# NU32v7.net
KiCad netlist of a schematic drawn in EAGLE
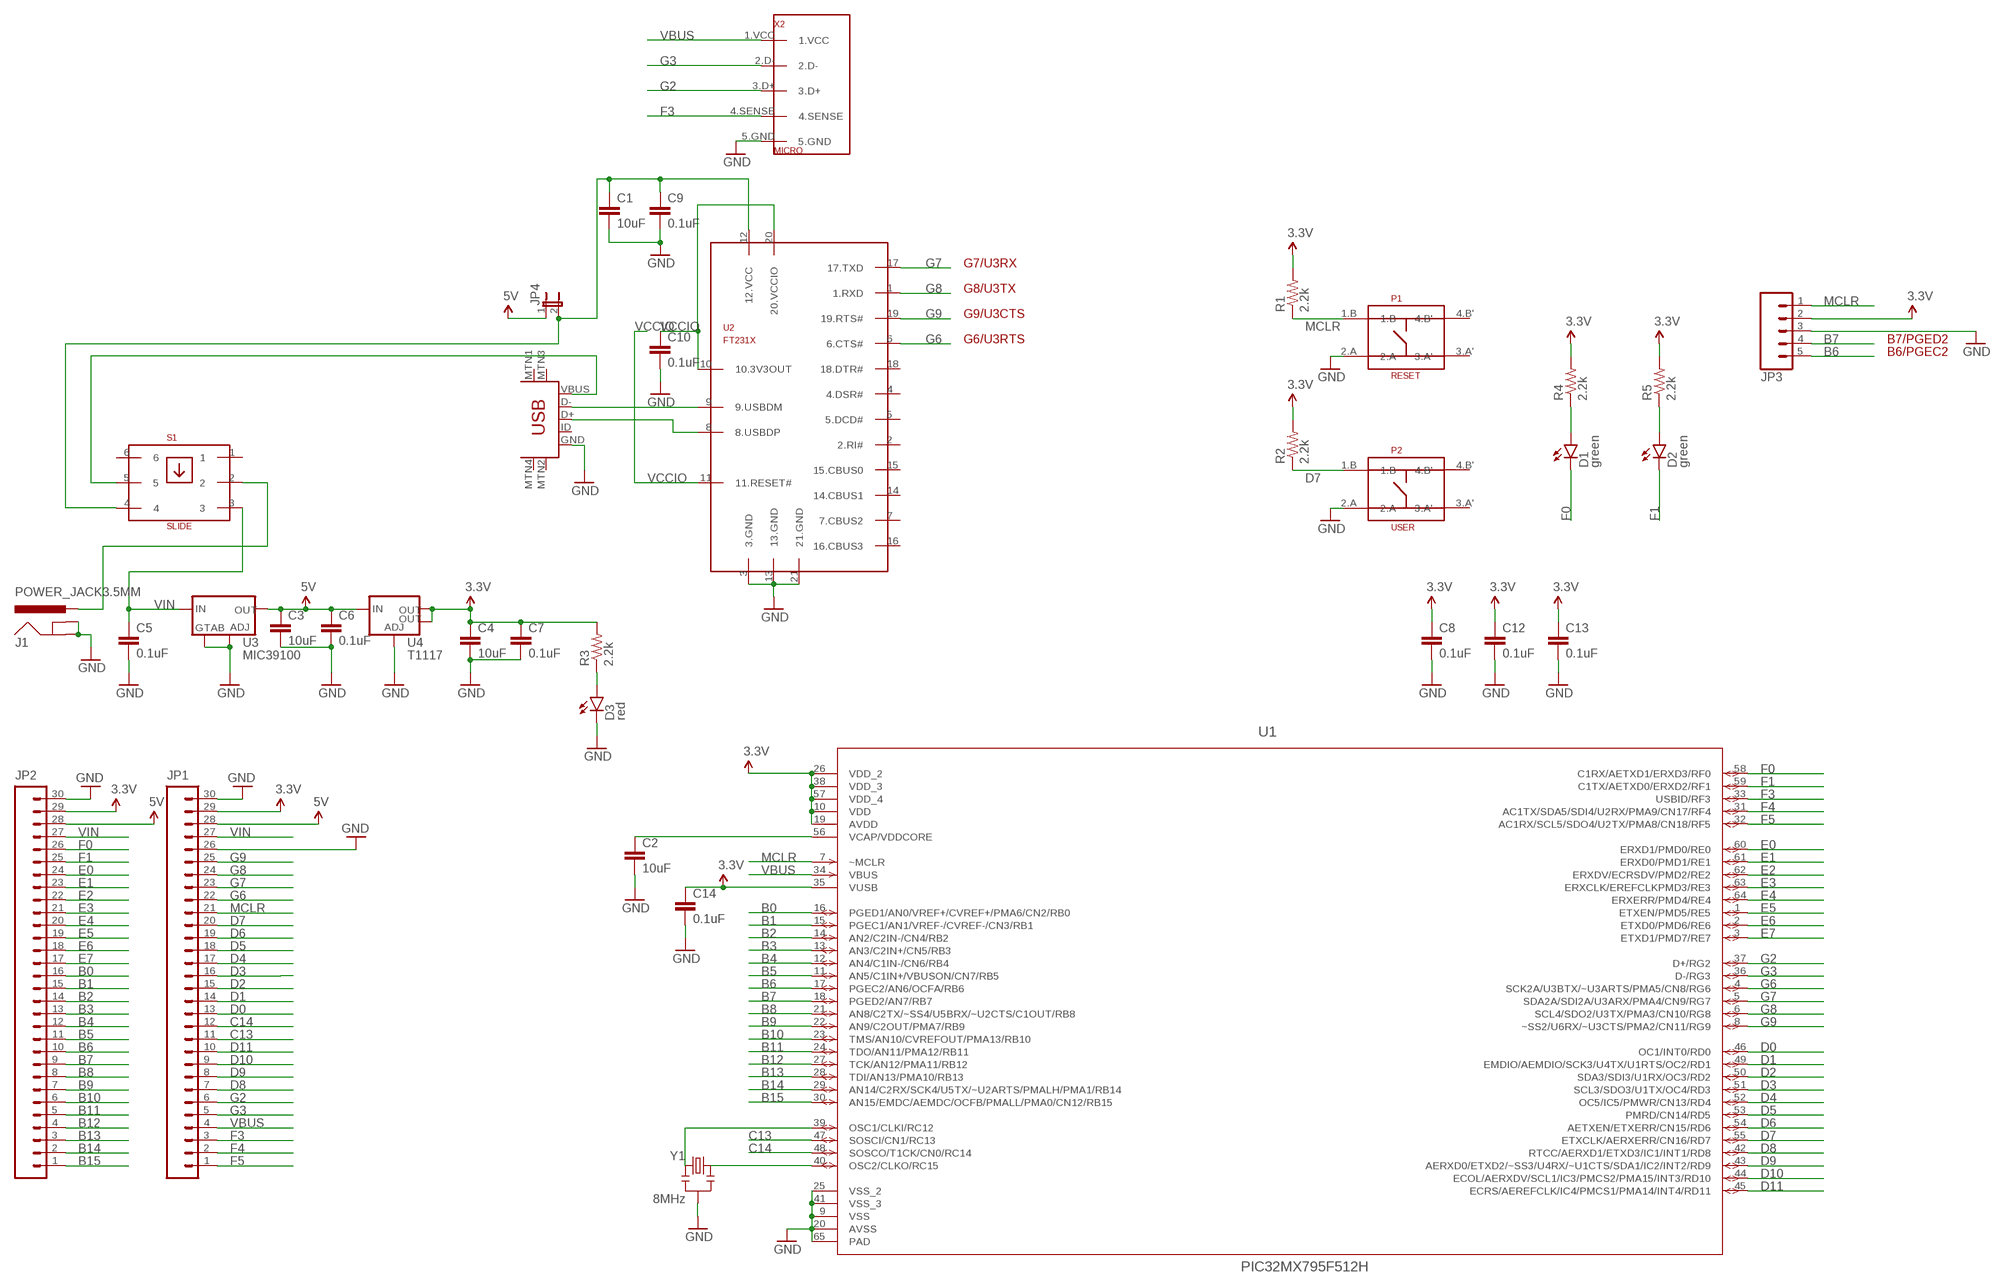
[diagram p0: schematic, sheet 1]

(export (version "E")
  (design (tool "Eeschema 10.0.6"))
  (components
    (comp (ref "C1")
      (value "10uF")
      (footprint "eagle-import:0603-CAP")
      (libsource (lib "eagle-import") (part "10UF-6.3V-20%(0603)"))
    )
    (comp (ref "C2")
      (value "10uF")
      (footprint "eagle-import:0603-CAP")
      (libsource (lib "eagle-import") (part "10UF-6.3V-20%(0603)"))
    )
    (comp (ref "C3")
      (value "10uF")
      (footprint "eagle-import:0603-CAP")
      (libsource (lib "eagle-import") (part "10UF-6.3V-20%(0603)"))
    )
    (comp (ref "C4")
      (value "10uF")
      (footprint "eagle-import:0603-CAP")
      (libsource (lib "eagle-import") (part "10UF-6.3V-20%(0603)"))
    )
    (comp (ref "C5")
      (value "0.1uF")
      (footprint "eagle-import:0603-CAP")
      (libsource (lib "eagle-import") (part "CAP0603-CAP"))
    )
    (comp (ref "C6")
      (value "0.1uF")
      (footprint "eagle-import:0603-CAP")
      (libsource (lib "eagle-import") (part "CAP0603-CAP"))
    )
    (comp (ref "C7")
      (value "0.1uF")
      (footprint "eagle-import:0603-CAP")
      (libsource (lib "eagle-import") (part "CAP0603-CAP"))
    )
    (comp (ref "C8")
      (value "0.1uF")
      (footprint "eagle-import:0603-CAP")
      (libsource (lib "eagle-import") (part "CAP0603-CAP"))
    )
    (comp (ref "C9")
      (value "0.1uF")
      (footprint "eagle-import:0603-CAP")
      (libsource (lib "eagle-import") (part "CAP0603-CAP"))
    )
    (comp (ref "C10")
      (value "0.1uF")
      (footprint "eagle-import:0603-CAP")
      (libsource (lib "eagle-import") (part "CAP0603-CAP"))
    )
    (comp (ref "C12")
      (value "0.1uF")
      (footprint "eagle-import:0603-CAP")
      (libsource (lib "eagle-import") (part "CAP0603-CAP"))
    )
    (comp (ref "C13")
      (value "0.1uF")
      (footprint "eagle-import:0603-CAP")
      (libsource (lib "eagle-import") (part "CAP0603-CAP"))
    )
    (comp (ref "C14")
      (value "0.1uF")
      (footprint "eagle-import:0603-CAP")
      (libsource (lib "eagle-import") (part "CAP0603-CAP"))
    )
    (comp (ref "D1")
      (value "green")
      (footprint "eagle-import:LED-0603")
      (libsource (lib "eagle-import") (part "LED0603"))
    )
    (comp (ref "D2")
      (value "green")
      (footprint "eagle-import:LED-0603")
      (libsource (lib "eagle-import") (part "LED0603"))
    )
    (comp (ref "D3")
      (value "red")
      (footprint "eagle-import:LED-0603")
      (libsource (lib "eagle-import") (part "LED0603"))
    )
    (comp (ref "J1")
      (value "POWER_JACK3.5MM")
      (footprint "eagle-import:POWER_JACK_3.5MM")
      (libsource (lib "eagle-import") (part "POWER_JACK3.5MM"))
    )
    (comp (ref "JP1")
      (value "M30NO_SILK")
      (footprint "eagle-import:1X30_NO_SILK")
      (libsource (lib "eagle-import") (part "M30NO_SILK"))
    )
    (comp (ref "JP2")
      (value "M30NO_SILK")
      (footprint "eagle-import:1X30_NO_SILK")
      (libsource (lib "eagle-import") (part "M30NO_SILK"))
    )
    (comp (ref "JP3")
      (value "M05PTH")
      (footprint "eagle-import:1X05")
      (libsource (lib "eagle-import") (part "M05PTH"))
    )
    (comp (ref "JP4")
      (value "JUMPER-2SMD-NO")
      (footprint "eagle-import:SJ_2S-NO")
      (libsource (lib "eagle-import") (part "JUMPER-2SMD-NO"))
    )
    (comp (ref "P1")
      (value "RESET")
      (footprint "eagle-import:MOM_SW")
      (libsource (lib "eagle-import") (part "MOM_SW"))
    )
    (comp (ref "P2")
      (value "USER")
      (footprint "eagle-import:MOM_SW")
      (libsource (lib "eagle-import") (part "MOM_SW"))
    )
    (comp (ref "R1")
      (value "2.2k")
      (footprint "eagle-import:0603-RES")
      (libsource (lib "eagle-import") (part "RESISTOR0603"))
    )
    (comp (ref "R2")
      (value "2.2k")
      (footprint "eagle-import:0603-RES")
      (libsource (lib "eagle-import") (part "RESISTOR0603"))
    )
    (comp (ref "R3")
      (value "2.2k")
      (footprint "eagle-import:0603-RES")
      (libsource (lib "eagle-import") (part "RESISTOR0603"))
    )
    (comp (ref "R4")
      (value "2.2k")
      (footprint "eagle-import:0603-RES")
      (libsource (lib "eagle-import") (part "RESISTOR0603"))
    )
    (comp (ref "R5")
      (value "2.2k")
      (footprint "eagle-import:0603-RES")
      (libsource (lib "eagle-import") (part "RESISTOR0603"))
    )
    (comp (ref "S1")
      (value "SLIDE")
      (footprint "eagle-import:SLIDE_SW")
      (libsource (lib "eagle-import") (part "SLIDE_SW"))
    )
    (comp (ref "U1")
      (value "PIC32MX795F512H")
      (footprint "eagle-import:QFN50P900X900X100-65N")
      (libsource (lib "eagle-import") (part "PIC32MX795F512H-80I/PTQFN"))
    )
    (comp (ref "U2")
      (value "FT231X")
      (footprint "eagle-import:QFN50P400X400X100-21N")
      (libsource (lib "eagle-import") (part "FT231X"))
    )
    (comp (ref "U3")
      (value "MIC39100")
      (footprint "eagle-import:SOT223")
      (libsource (lib "eagle-import") (part "MIC39100"))
    )
    (comp (ref "U4")
      (value "T1117")
      (footprint "eagle-import:SOT223")
      (libsource (lib "eagle-import") (part "V_REG_LM1117SOT223"))
    )
    (comp (ref "X1")
      (value "MINI")
      (footprint "eagle-import:USB-MINIB")
      (libsource (lib "eagle-import") (part "USB-MINIB-5PIN"))
    )
    (comp (ref "X2")
      (value "MICRO")
      (footprint "eagle-import:MICROUSB")
      (libsource (lib "eagle-import") (part "MICROUSB"))
    )
    (comp (ref "Y1")
      (value "8MHz")
      (footprint "eagle-import:RESONATOR-SMD")
      (libsource (lib "eagle-import") (part "RESONATORSMD"))
    )
  )
  (nets
    (net (code "1") (name "/B0") (class "Default")
      (node (ref "JP2") (pin "16") (pinfunction "16_16") (pintype "passive"))
      (node (ref "U1") (pin "16") (pinfunction "PGED1/AN0/VREF+/CVREF+/PMA6/CN2/RB0_16") (pintype "bidirectional"))
    )
    (net (code "2") (name "/B1") (class "Default")
      (node (ref "JP2") (pin "15") (pinfunction "15_15") (pintype "passive"))
      (node (ref "U1") (pin "15") (pinfunction "PGEC1/AN1/VREF-/CVREF-/CN3/RB1_15") (pintype "bidirectional"))
    )
    (net (code "3") (name "/B2") (class "Default")
      (node (ref "JP2") (pin "14") (pinfunction "14_14") (pintype "passive"))
      (node (ref "U1") (pin "14") (pinfunction "AN2/C2IN-/CN4/RB2_14") (pintype "bidirectional"))
    )
    (net (code "4") (name "/B3") (class "Default")
      (node (ref "JP2") (pin "13") (pinfunction "13_13") (pintype "passive"))
      (node (ref "U1") (pin "13") (pinfunction "AN3/C2IN+/CN5/RB3_13") (pintype "bidirectional"))
    )
    (net (code "5") (name "/B4") (class "Default")
      (node (ref "JP2") (pin "12") (pinfunction "12_12") (pintype "passive"))
      (node (ref "U1") (pin "12") (pinfunction "AN4/C1IN-/CN6/RB4_12") (pintype "bidirectional"))
    )
    (net (code "6") (name "/B5") (class "Default")
      (node (ref "JP2") (pin "11") (pinfunction "11_11") (pintype "passive"))
      (node (ref "U1") (pin "11") (pinfunction "AN5/C1IN+/VBUSON/CN7/RB5_11") (pintype "bidirectional"))
    )
    (net (code "7") (name "/B6") (class "Default")
      (node (ref "JP2") (pin "10") (pinfunction "10_10") (pintype "passive"))
      (node (ref "JP3") (pin "5") (pinfunction "5_5") (pintype "passive"))
      (node (ref "U1") (pin "17") (pinfunction "PGEC2/AN6/OCFA/RB6_17") (pintype "bidirectional"))
    )
    (net (code "8") (name "/B7") (class "Default")
      (node (ref "JP2") (pin "9") (pinfunction "9_9") (pintype "passive"))
      (node (ref "JP3") (pin "4") (pinfunction "4_4") (pintype "passive"))
      (node (ref "U1") (pin "18") (pinfunction "PGED2/AN7/RB7_18") (pintype "bidirectional"))
    )
    (net (code "9") (name "/B8") (class "Default")
      (node (ref "JP2") (pin "8") (pinfunction "8_8") (pintype "passive"))
      (node (ref "U1") (pin "21") (pinfunction "AN8/C2TX/~{SS4/U5BRX/}U2CTS/C1OUT/RB8_21") (pintype "bidirectional"))
    )
    (net (code "10") (name "/B9") (class "Default")
      (node (ref "JP2") (pin "7") (pinfunction "7_7") (pintype "passive"))
      (node (ref "U1") (pin "22") (pinfunction "AN9/C2OUT/PMA7/RB9_22") (pintype "bidirectional"))
    )
    (net (code "11") (name "/B10") (class "Default")
      (node (ref "JP2") (pin "6") (pinfunction "6_6") (pintype "passive"))
      (node (ref "U1") (pin "23") (pinfunction "TMS/AN10/CVREFOUT/PMA13/RB10_23") (pintype "bidirectional"))
    )
    (net (code "12") (name "/B11") (class "Default")
      (node (ref "JP2") (pin "5") (pinfunction "5_5") (pintype "passive"))
      (node (ref "U1") (pin "24") (pinfunction "TDO/AN11/PMA12/RB11_24") (pintype "bidirectional"))
    )
    (net (code "13") (name "/B12") (class "Default")
      (node (ref "JP2") (pin "4") (pinfunction "4_4") (pintype "passive"))
      (node (ref "U1") (pin "27") (pinfunction "TCK/AN12/PMA11/RB12_27") (pintype "bidirectional"))
    )
    (net (code "14") (name "/B13") (class "Default")
      (node (ref "JP2") (pin "3") (pinfunction "3_3") (pintype "passive"))
      (node (ref "U1") (pin "28") (pinfunction "TDI/AN13/PMA10/RB13_28") (pintype "bidirectional"))
    )
    (net (code "15") (name "/B14") (class "Default")
      (node (ref "JP2") (pin "2") (pinfunction "2_2") (pintype "passive"))
      (node (ref "U1") (pin "29") (pinfunction "AN14/C2RX/SCK4/U5TX/~{U2ARTS/PMALH/PMA1/RB14}_29") (pintype "bidirectional"))
    )
    (net (code "16") (name "/B15") (class "Default")
      (node (ref "JP2") (pin "1") (pinfunction "1_1") (pintype "passive"))
      (node (ref "U1") (pin "30") (pinfunction "AN15/EMDC/AEMDC/OCFB/PMALL/PMA0/CN12/RB15_30") (pintype "bidirectional"))
    )
    (net (code "17") (name "/C13") (class "Default")
      (node (ref "JP1") (pin "11") (pinfunction "11_11") (pintype "passive"))
      (node (ref "U1") (pin "47") (pinfunction "SOSCI/CN1/RC13_47") (pintype "bidirectional"))
    )
    (net (code "18") (name "/C14") (class "Default")
      (node (ref "JP1") (pin "12") (pinfunction "12_12") (pintype "passive"))
      (node (ref "U1") (pin "48") (pinfunction "SOSCO/T1CK/CN0/RC14_48") (pintype "bidirectional"))
    )
    (net (code "19") (name "/D0") (class "Default")
      (node (ref "JP1") (pin "13") (pinfunction "13_13") (pintype "passive"))
      (node (ref "U1") (pin "46") (pinfunction "OC1/INT0/RD0_46") (pintype "bidirectional"))
    )
    (net (code "20") (name "/D1") (class "Default")
      (node (ref "JP1") (pin "14") (pinfunction "14_14") (pintype "passive"))
      (node (ref "U1") (pin "49") (pinfunction "EMDIO/AEMDIO/SCK3/U4TX/U1RTS/OC2/RD1_49") (pintype "bidirectional"))
    )
    (net (code "21") (name "/D2") (class "Default")
      (node (ref "JP1") (pin "15") (pinfunction "15_15") (pintype "passive"))
      (node (ref "U1") (pin "50") (pinfunction "SDA3/SDI3/U1RX/OC3/RD2_50") (pintype "bidirectional"))
    )
    (net (code "22") (name "/D3") (class "Default")
      (node (ref "JP1") (pin "16") (pinfunction "16_16") (pintype "passive"))
      (node (ref "U1") (pin "51") (pinfunction "SCL3/SDO3/U1TX/OC4/RD3_51") (pintype "bidirectional"))
    )
    (net (code "23") (name "/D4") (class "Default")
      (node (ref "JP1") (pin "17") (pinfunction "17_17") (pintype "passive"))
      (node (ref "U1") (pin "52") (pinfunction "OC5/IC5/PMWR/CN13/RD4_52") (pintype "bidirectional"))
    )
    (net (code "24") (name "/D5") (class "Default")
      (node (ref "JP1") (pin "18") (pinfunction "18_18") (pintype "passive"))
      (node (ref "U1") (pin "53") (pinfunction "PMRD/CN14/RD5_53") (pintype "bidirectional"))
    )
    (net (code "25") (name "/D6") (class "Default")
      (node (ref "JP1") (pin "19") (pinfunction "19_19") (pintype "passive"))
      (node (ref "U1") (pin "54") (pinfunction "AETXEN/ETXERR/CN15/RD6_54") (pintype "bidirectional"))
    )
    (net (code "26") (name "/D7") (class "Default")
      (node (ref "JP1") (pin "20") (pinfunction "20_20") (pintype "passive"))
      (node (ref "P2") (pin "1.B") (pinfunction "1.B_1.B") (pintype "bidirectional"))
      (node (ref "R2") (pin "1") (pinfunction "1_1") (pintype "passive"))
      (node (ref "U1") (pin "55") (pinfunction "ETXCLK/AERXERR/CN16/RD7_55") (pintype "bidirectional"))
    )
    (net (code "27") (name "/D8") (class "Default")
      (node (ref "JP1") (pin "7") (pinfunction "7_7") (pintype "passive"))
      (node (ref "U1") (pin "42") (pinfunction "RTCC/AERXD1/ETXD3/IC1/INT1/RD8_42") (pintype "bidirectional"))
    )
    (net (code "28") (name "/D9") (class "Default")
      (node (ref "JP1") (pin "8") (pinfunction "8_8") (pintype "passive"))
      (node (ref "U1") (pin "43") (pinfunction "AERXD0/ETXD2/~{SS3/U4RX/}U1CTS/SDA1/IC2/INT2/RD9_43") (pintype "bidirectional"))
    )
    (net (code "29") (name "/D10") (class "Default")
      (node (ref "JP1") (pin "9") (pinfunction "9_9") (pintype "passive"))
      (node (ref "U1") (pin "44") (pinfunction "ECOL/AERXDV/SCL1/IC3/PMCS2/PMA15/INT3/RD10_44") (pintype "bidirectional"))
    )
    (net (code "30") (name "/D11") (class "Default")
      (node (ref "JP1") (pin "10") (pinfunction "10_10") (pintype "passive"))
      (node (ref "U1") (pin "45") (pinfunction "ECRS/AEREFCLK/IC4/PMCS1/PMA14/INT4/RD11_45") (pintype "bidirectional"))
    )
    (net (code "31") (name "/E0") (class "Default")
      (node (ref "JP2") (pin "24") (pinfunction "24_24") (pintype "passive"))
      (node (ref "U1") (pin "60") (pinfunction "ERXD1/PMD0/RE0_60") (pintype "bidirectional"))
    )
    (net (code "32") (name "/E1") (class "Default")
      (node (ref "JP2") (pin "23") (pinfunction "23_23") (pintype "passive"))
      (node (ref "U1") (pin "61") (pinfunction "ERXD0/PMD1/RE1_61") (pintype "bidirectional"))
    )
    (net (code "33") (name "/E2") (class "Default")
      (node (ref "JP2") (pin "22") (pinfunction "22_22") (pintype "passive"))
      (node (ref "U1") (pin "62") (pinfunction "ERXDV/ECRSDV/PMD2/RE2_62") (pintype "bidirectional"))
    )
    (net (code "34") (name "/E3") (class "Default")
      (node (ref "JP2") (pin "21") (pinfunction "21_21") (pintype "passive"))
      (node (ref "U1") (pin "63") (pinfunction "ERXCLK/EREFCLKPMD3/RE3_63") (pintype "bidirectional"))
    )
    (net (code "35") (name "/E4") (class "Default")
      (node (ref "JP2") (pin "20") (pinfunction "20_20") (pintype "passive"))
      (node (ref "U1") (pin "64") (pinfunction "ERXERR/PMD4/RE4_64") (pintype "bidirectional"))
    )
    (net (code "36") (name "/E5") (class "Default")
      (node (ref "JP2") (pin "19") (pinfunction "19_19") (pintype "passive"))
      (node (ref "U1") (pin "1") (pinfunction "ETXEN/PMD5/RE5_1") (pintype "bidirectional"))
    )
    (net (code "37") (name "/E6") (class "Default")
      (node (ref "JP2") (pin "18") (pinfunction "18_18") (pintype "passive"))
      (node (ref "U1") (pin "2") (pinfunction "ETXD0/PMD6/RE6_2") (pintype "bidirectional"))
    )
    (net (code "38") (name "/E7") (class "Default")
      (node (ref "JP2") (pin "17") (pinfunction "17_17") (pintype "passive"))
      (node (ref "U1") (pin "3") (pinfunction "ETXD1/PMD7/RE7_3") (pintype "bidirectional"))
    )
    (net (code "39") (name "/F0") (class "Default")
      (node (ref "D1") (pin "C") (pinfunction "C_C") (pintype "passive"))
      (node (ref "JP2") (pin "26") (pinfunction "26_26") (pintype "passive"))
      (node (ref "U1") (pin "58") (pinfunction "C1RX/AETXD1/ERXD3/RF0_58") (pintype "bidirectional"))
    )
    (net (code "40") (name "/F1") (class "Default")
      (node (ref "D2") (pin "C") (pinfunction "C_C") (pintype "passive"))
      (node (ref "JP2") (pin "25") (pinfunction "25_25") (pintype "passive"))
      (node (ref "U1") (pin "59") (pinfunction "C1TX/AETXD0/ERXD2/RF1_59") (pintype "bidirectional"))
    )
    (net (code "41") (name "/F3") (class "Default")
      (node (ref "JP1") (pin "3") (pinfunction "3_3") (pintype "passive"))
      (node (ref "U1") (pin "33") (pinfunction "USBID/RF3_33") (pintype "bidirectional"))
      (node (ref "X2") (pin "4.SENSE") (pinfunction "4.SENSE_4.SENSE") (pintype "bidirectional"))
    )
    (net (code "42") (name "/F4") (class "Default")
      (node (ref "JP1") (pin "2") (pinfunction "2_2") (pintype "passive"))
      (node (ref "U1") (pin "31") (pinfunction "AC1TX/SDA5/SDI4/U2RX/PMA9/CN17/RF4_31") (pintype "bidirectional"))
    )
    (net (code "43") (name "/F5") (class "Default")
      (node (ref "JP1") (pin "1") (pinfunction "1_1") (pintype "passive"))
      (node (ref "U1") (pin "32") (pinfunction "AC1RX/SCL5/SDO4/U2TX/PMA8/CN18/RF5_32") (pintype "bidirectional"))
    )
    (net (code "44") (name "/G2") (class "Default")
      (node (ref "JP1") (pin "6") (pinfunction "6_6") (pintype "passive"))
      (node (ref "U1") (pin "37") (pinfunction "D+/RG2_37") (pintype "bidirectional"))
      (node (ref "X2") (pin "3.D+") (pinfunction "3.D+_3.D+") (pintype "bidirectional"))
    )
    (net (code "45") (name "/G3") (class "Default")
      (node (ref "JP1") (pin "5") (pinfunction "5_5") (pintype "passive"))
      (node (ref "U1") (pin "36") (pinfunction "D-/RG3_36") (pintype "bidirectional"))
      (node (ref "X2") (pin "2.D-") (pinfunction "2.D-_2.D-") (pintype "bidirectional"))
    )
    (net (code "46") (name "/G6") (class "Default")
      (node (ref "JP1") (pin "22") (pinfunction "22_22") (pintype "passive"))
      (node (ref "U1") (pin "4") (pinfunction "SCK2A/U3BTX/~{U3ARTS/PMA5/CN8/RG6}_4") (pintype "bidirectional"))
      (node (ref "U2") (pin "6") (pinfunction "6.CTS#_6") (pintype "bidirectional"))
    )
    (net (code "47") (name "/G7") (class "Default")
      (node (ref "JP1") (pin "23") (pinfunction "23_23") (pintype "passive"))
      (node (ref "U1") (pin "5") (pinfunction "SDA2A/SDI2A/U3ARX/PMA4/CN9/RG7_5") (pintype "bidirectional"))
      (node (ref "U2") (pin "17") (pinfunction "17.TXD_17") (pintype "bidirectional"))
    )
    (net (code "48") (name "/G8") (class "Default")
      (node (ref "JP1") (pin "24") (pinfunction "24_24") (pintype "passive"))
      (node (ref "U1") (pin "6") (pinfunction "SCL4/SDO2/U3TX/PMA3/CN10/RG8_6") (pintype "bidirectional"))
      (node (ref "U2") (pin "1") (pinfunction "1.RXD_1") (pintype "bidirectional"))
    )
    (net (code "49") (name "/G9") (class "Default")
      (node (ref "JP1") (pin "25") (pinfunction "25_25") (pintype "passive"))
      (node (ref "U1") (pin "8") (pinfunction "~{SS2/U6RX/}U3CTS/PMA2/CN11/RG9_8") (pintype "bidirectional"))
      (node (ref "U2") (pin "19") (pinfunction "19.RTS#_19") (pintype "bidirectional"))
    )
    (net (code "50") (name "/MCLR") (class "Default")
      (node (ref "JP1") (pin "21") (pinfunction "21_21") (pintype "passive"))
      (node (ref "JP3") (pin "1") (pinfunction "1_1") (pintype "passive"))
      (node (ref "P1") (pin "1.B") (pinfunction "1.B_1.B") (pintype "bidirectional"))
      (node (ref "R1") (pin "1") (pinfunction "1_1") (pintype "passive"))
      (node (ref "U1") (pin "7") (pinfunction "~{MCLR}_7") (pintype "input"))
    )
    (net (code "51") (name "/VBUS") (class "Default")
      (node (ref "JP1") (pin "4") (pinfunction "4_4") (pintype "passive"))
      (node (ref "U1") (pin "34") (pinfunction "VBUS_34") (pintype "input"))
      (node (ref "X2") (pin "1.VCC") (pinfunction "1.VCC_1.VCC") (pintype "bidirectional"))
    )
    (net (code "52") (name "/VCCIO") (class "Default")
      (node (ref "C10") (pin "1") (pinfunction "1_1") (pintype "passive"))
      (node (ref "U2") (pin "10") (pinfunction "10.3V3OUT_10") (pintype "bidirectional"))
      (node (ref "U2") (pin "11") (pinfunction "11.RESET#_11") (pintype "bidirectional"))
      (node (ref "U2") (pin "20") (pinfunction "20.VCCIO_20") (pintype "bidirectional"))
    )
    (net (code "53") (name "/VIN") (class "Default")
      (node (ref "C5") (pin "1") (pinfunction "1_1") (pintype "passive"))
      (node (ref "JP1") (pin "27") (pinfunction "27_27") (pintype "passive"))
      (node (ref "JP2") (pin "27") (pinfunction "27_27") (pintype "passive"))
      (node (ref "S1") (pin "3") (pinfunction "3_3") (pintype "bidirectional"))
      (node (ref "U3") (pin "1") (pinfunction "IN_1") (pintype "input"))
    )
    (net (code "54") (name "3.3V") (class "Default")
      (node (ref "C12") (pin "1") (pinfunction "1_1") (pintype "passive"))
      (node (ref "C13") (pin "1") (pinfunction "1_1") (pintype "passive"))
      (node (ref "C14") (pin "1") (pinfunction "1_1") (pintype "passive"))
      (node (ref "C4") (pin "1") (pinfunction "1_1") (pintype "passive"))
      (node (ref "C7") (pin "1") (pinfunction "1_1") (pintype "passive"))
      (node (ref "C8") (pin "1") (pinfunction "1_1") (pintype "passive"))
      (node (ref "JP1") (pin "29") (pinfunction "29_29") (pintype "passive"))
      (node (ref "JP2") (pin "29") (pinfunction "29_29") (pintype "passive"))
      (node (ref "JP3") (pin "2") (pinfunction "2_2") (pintype "passive"))
      (node (ref "R1") (pin "2") (pinfunction "2_2") (pintype "passive"))
      (node (ref "R2") (pin "2") (pinfunction "2_2") (pintype "passive"))
      (node (ref "R3") (pin "2") (pinfunction "2_2") (pintype "passive"))
      (node (ref "R4") (pin "2") (pinfunction "2_2") (pintype "passive"))
      (node (ref "R5") (pin "2") (pinfunction "2_2") (pintype "passive"))
      (node (ref "U1") (pin "10") (pinfunction "VDD_10") (pintype "power_in"))
      (node (ref "U1") (pin "19") (pinfunction "AVDD_19") (pintype "power_in"))
      (node (ref "U1") (pin "26") (pinfunction "VDD_2_26") (pintype "power_in"))
      (node (ref "U1") (pin "35") (pinfunction "VUSB_35") (pintype "power_in"))
      (node (ref "U1") (pin "38") (pinfunction "VDD_3_38") (pintype "power_in"))
      (node (ref "U1") (pin "57") (pinfunction "VDD_4_57") (pintype "power_in"))
      (node (ref "U4") (pin "2") (pinfunction "OUT_2") (pintype "output"))
      (node (ref "U4") (pin "4") (pinfunction "OUT_4") (pintype "output"))
    )
    (net (code "55") (name "5V") (class "Default")
      (node (ref "C3") (pin "1") (pinfunction "1_1") (pintype "passive"))
      (node (ref "C6") (pin "1") (pinfunction "1_1") (pintype "passive"))
      (node (ref "JP1") (pin "28") (pinfunction "28_28") (pintype "passive"))
      (node (ref "JP2") (pin "28") (pinfunction "28_28") (pintype "passive"))
      (node (ref "JP4") (pin "1") (pinfunction "1_1") (pintype "passive"))
      (node (ref "U3") (pin "3") (pinfunction "OUT_3") (pintype "output"))
      (node (ref "U4") (pin "3") (pinfunction "IN_3") (pintype "input"))
    )
    (net (code "56") (name "GND") (class "Default")
      (node (ref "C1") (pin "2") (pinfunction "2_2") (pintype "passive"))
      (node (ref "C10") (pin "2") (pinfunction "2_2") (pintype "passive"))
      (node (ref "C12") (pin "2") (pinfunction "2_2") (pintype "passive"))
      (node (ref "C13") (pin "2") (pinfunction "2_2") (pintype "passive"))
      (node (ref "C14") (pin "2") (pinfunction "2_2") (pintype "passive"))
      (node (ref "C2") (pin "2") (pinfunction "2_2") (pintype "passive"))
      (node (ref "C3") (pin "2") (pinfunction "2_2") (pintype "passive"))
      (node (ref "C4") (pin "2") (pinfunction "2_2") (pintype "passive"))
      (node (ref "C5") (pin "2") (pinfunction "2_2") (pintype "passive"))
      (node (ref "C6") (pin "2") (pinfunction "2_2") (pintype "passive"))
      (node (ref "C7") (pin "2") (pinfunction "2_2") (pintype "passive"))
      (node (ref "C8") (pin "2") (pinfunction "2_2") (pintype "passive"))
      (node (ref "C9") (pin "2") (pinfunction "2_2") (pintype "passive"))
      (node (ref "D3") (pin "C") (pinfunction "C_C") (pintype "passive"))
      (node (ref "J1") (pin "2.GND") (pinfunction "GND_2.GND") (pintype "bidirectional"))
      (node (ref "J1") (pin "3.GNDBREAK") (pinfunction "GNDBREAK_3.GNDBREAK") (pintype "bidirectional"))
      (node (ref "JP1") (pin "26") (pinfunction "26_26") (pintype "passive"))
      (node (ref "JP1") (pin "30") (pinfunction "30_30") (pintype "passive"))
      (node (ref "JP2") (pin "30") (pinfunction "30_30") (pintype "passive"))
      (node (ref "JP3") (pin "3") (pinfunction "3_3") (pintype "passive"))
      (node (ref "P1") (pin "2.A") (pinfunction "2.A_2.A") (pintype "bidirectional"))
      (node (ref "P2") (pin "2.A") (pinfunction "2.A_2.A") (pintype "bidirectional"))
      (node (ref "U1") (pin "20") (pinfunction "AVSS_20") (pintype "power_in"))
      (node (ref "U1") (pin "25") (pinfunction "VSS_2_25") (pintype "power_in"))
      (node (ref "U1") (pin "41") (pinfunction "VSS_3_41") (pintype "power_in"))
      (node (ref "U1") (pin "65") (pinfunction "PAD_65") (pintype "bidirectional"))
      (node (ref "U1") (pin "9") (pinfunction "VSS_9") (pintype "power_in"))
      (node (ref "U2") (pin "13") (pinfunction "13.GND_13") (pintype "bidirectional"))
      (node (ref "U2") (pin "21") (pinfunction "21.GND_21") (pintype "bidirectional"))
      (node (ref "U2") (pin "3") (pinfunction "3.GND_3") (pintype "bidirectional"))
      (node (ref "U3") (pin "2") (pinfunction "ADJ_2") (pintype "input"))
      (node (ref "U3") (pin "4") (pinfunction "TAB_4") (pintype "output"))
      (node (ref "U4") (pin "1") (pinfunction "ADJ_1") (pintype "input"))
      (node (ref "X1") (pin "GND") (pinfunction "GND_GND") (pintype "bidirectional"))
      (node (ref "X2") (pin "5.GND") (pinfunction "5.GND_5.GND") (pintype "bidirectional"))
      (node (ref "Y1") (pin "2") (pinfunction "2_2") (pintype "passive"))
    )
    (net (code "57") (name "Net-(D1-PadA)") (class "Default")
      (node (ref "D1") (pin "A") (pinfunction "A_A") (pintype "passive"))
      (node (ref "R4") (pin "1") (pinfunction "1_1") (pintype "passive"))
    )
    (net (code "58") (name "Net-(D2-PadA)") (class "Default")
      (node (ref "D2") (pin "A") (pinfunction "A_A") (pintype "passive"))
      (node (ref "R5") (pin "1") (pinfunction "1_1") (pintype "passive"))
    )
    (net (code "59") (name "Net-(D3-PadA)") (class "Default")
      (node (ref "D3") (pin "A") (pinfunction "A_A") (pintype "passive"))
      (node (ref "R3") (pin "1") (pinfunction "1_1") (pintype "passive"))
    )
    (net (code "60") (name "Net-(J1-PWR)") (class "Default")
      (node (ref "J1") (pin "1.POWER") (pinfunction "PWR_1.POWER") (pintype "bidirectional"))
      (node (ref "S1") (pin "2") (pinfunction "2_2") (pintype "bidirectional"))
    )
    (net (code "61") (name "Net-(S1-Pad5)") (class "Default")
      (node (ref "S1") (pin "5") (pinfunction "5_5") (pintype "bidirectional"))
      (node (ref "X1") (pin "VBUS") (pinfunction "VBUS_VBUS") (pintype "bidirectional"))
    )
    (net (code "62") (name "Net-(U1-OSC1{slash}CLKI{slash}RC12)") (class "Default")
      (node (ref "U1") (pin "39") (pinfunction "OSC1/CLKI/RC12_39") (pintype "bidirectional"))
      (node (ref "Y1") (pin "3") (pinfunction "3_3") (pintype "passive"))
    )
    (net (code "63") (name "Net-(U1-OSC2{slash}CLKO{slash}RC15)") (class "Default")
      (node (ref "U1") (pin "40") (pinfunction "OSC2/CLKO/RC15_40") (pintype "bidirectional"))
      (node (ref "Y1") (pin "1") (pinfunction "1_1") (pintype "passive"))
    )
    (net (code "64") (name "Net-(U1-VCAP{slash}VDDCORE)") (class "Default")
      (node (ref "C2") (pin "1") (pinfunction "1_1") (pintype "passive"))
      (node (ref "U1") (pin "56") (pinfunction "VCAP/VDDCORE_56") (pintype "power_in"))
    )
    (net (code "65") (name "Net-(U2-8.USBDP)") (class "Default")
      (node (ref "U2") (pin "8") (pinfunction "8.USBDP_8") (pintype "bidirectional"))
      (node (ref "X1") (pin "D+") (pinfunction "D+_D+") (pintype "bidirectional"))
    )
    (net (code "66") (name "Net-(U2-9.USBDM)") (class "Default")
      (node (ref "U2") (pin "9") (pinfunction "9.USBDM_9") (pintype "bidirectional"))
      (node (ref "X1") (pin "D-") (pinfunction "D-_D-") (pintype "bidirectional"))
    )
    (net (code "67") (name "Net-(U2-12.VCC)") (class "Default")
      (node (ref "C1") (pin "1") (pinfunction "1_1") (pintype "passive"))
      (node (ref "C9") (pin "1") (pinfunction "1_1") (pintype "passive"))
      (node (ref "JP4") (pin "2") (pinfunction "2_2") (pintype "passive"))
      (node (ref "S1") (pin "4") (pinfunction "4_4") (pintype "bidirectional"))
      (node (ref "U2") (pin "12") (pinfunction "12.VCC_12") (pintype "bidirectional"))
    )
    (net (code "68") (name "unconnected-(P1-Pad3.A')") (class "Default")
      (node (ref "P1") (pin "3.A'") (pinfunction "3.A'_3.A'") (pintype "bidirectional"))
    )
    (net (code "69") (name "unconnected-(P1-Pad4.B')") (class "Default")
      (node (ref "P1") (pin "4.B'") (pinfunction "4.B'_4.B'") (pintype "bidirectional"))
    )
    (net (code "70") (name "unconnected-(P2-Pad3.A')") (class "Default")
      (node (ref "P2") (pin "3.A'") (pinfunction "3.A'_3.A'") (pintype "bidirectional"))
    )
    (net (code "71") (name "unconnected-(P2-Pad4.B')") (class "Default")
      (node (ref "P2") (pin "4.B'") (pinfunction "4.B'_4.B'") (pintype "bidirectional"))
    )
    (net (code "72") (name "unconnected-(S1-Pad1)") (class "Default")
      (node (ref "S1") (pin "1") (pinfunction "1_1") (pintype "bidirectional"))
    )
    (net (code "73") (name "unconnected-(S1-Pad6)") (class "Default")
      (node (ref "S1") (pin "6") (pinfunction "6_6") (pintype "bidirectional"))
    )
    (net (code "74") (name "unconnected-(U2-2.RI#-Pad2)") (class "Default")
      (node (ref "U2") (pin "2") (pinfunction "2.RI#_2") (pintype "bidirectional"))
    )
    (net (code "75") (name "unconnected-(U2-4.DSR#-Pad4)") (class "Default")
      (node (ref "U2") (pin "4") (pinfunction "4.DSR#_4") (pintype "bidirectional"))
    )
    (net (code "76") (name "unconnected-(U2-5.DCD#-Pad5)") (class "Default")
      (node (ref "U2") (pin "5") (pinfunction "5.DCD#_5") (pintype "bidirectional"))
    )
    (net (code "77") (name "unconnected-(U2-7.CBUS2-Pad7)") (class "Default")
      (node (ref "U2") (pin "7") (pinfunction "7.CBUS2_7") (pintype "bidirectional"))
    )
    (net (code "78") (name "unconnected-(U2-14.CBUS1-Pad14)") (class "Default")
      (node (ref "U2") (pin "14") (pinfunction "14.CBUS1_14") (pintype "bidirectional"))
    )
    (net (code "79") (name "unconnected-(U2-15.CBUS0-Pad15)") (class "Default")
      (node (ref "U2") (pin "15") (pinfunction "15.CBUS0_15") (pintype "bidirectional"))
    )
    (net (code "80") (name "unconnected-(U2-16.CBUS3-Pad16)") (class "Default")
      (node (ref "U2") (pin "16") (pinfunction "16.CBUS3_16") (pintype "bidirectional"))
    )
    (net (code "81") (name "unconnected-(U2-18.DTR#-Pad18)") (class "Default")
      (node (ref "U2") (pin "18") (pinfunction "18.DTR#_18") (pintype "bidirectional"))
    )
    (net (code "82") (name "unconnected-(X1-MTN1-PadMTN3)") (class "Default")
      (node (ref "X1") (pin "MTN3") (pinfunction "MTN1_MTN3") (pintype "bidirectional"))
    )
    (net (code "83") (name "unconnected-(X1-MTN2-PadMTN1)") (class "Default")
      (node (ref "X1") (pin "MTN1") (pinfunction "MTN2_MTN1") (pintype "bidirectional"))
    )
    (net (code "84") (name "unconnected-(X1-MTN3-PadMTN2)") (class "Default")
      (node (ref "X1") (pin "MTN2") (pinfunction "MTN3_MTN2") (pintype "bidirectional"))
    )
    (net (code "85") (name "unconnected-(X1-PadID)") (class "Default")
      (node (ref "X1") (pin "ID") (pinfunction "ID_ID") (pintype "bidirectional"))
    )
    (net (code "86") (name "unconnected-(X1-PadMTN4)") (class "Default")
      (node (ref "X1") (pin "MTN4") (pinfunction "MTN4_MTN4") (pintype "bidirectional"))
    )
  )
)
